# WIFI2UART.net
KiCad netlist of a schematic drawn in Altium Designer
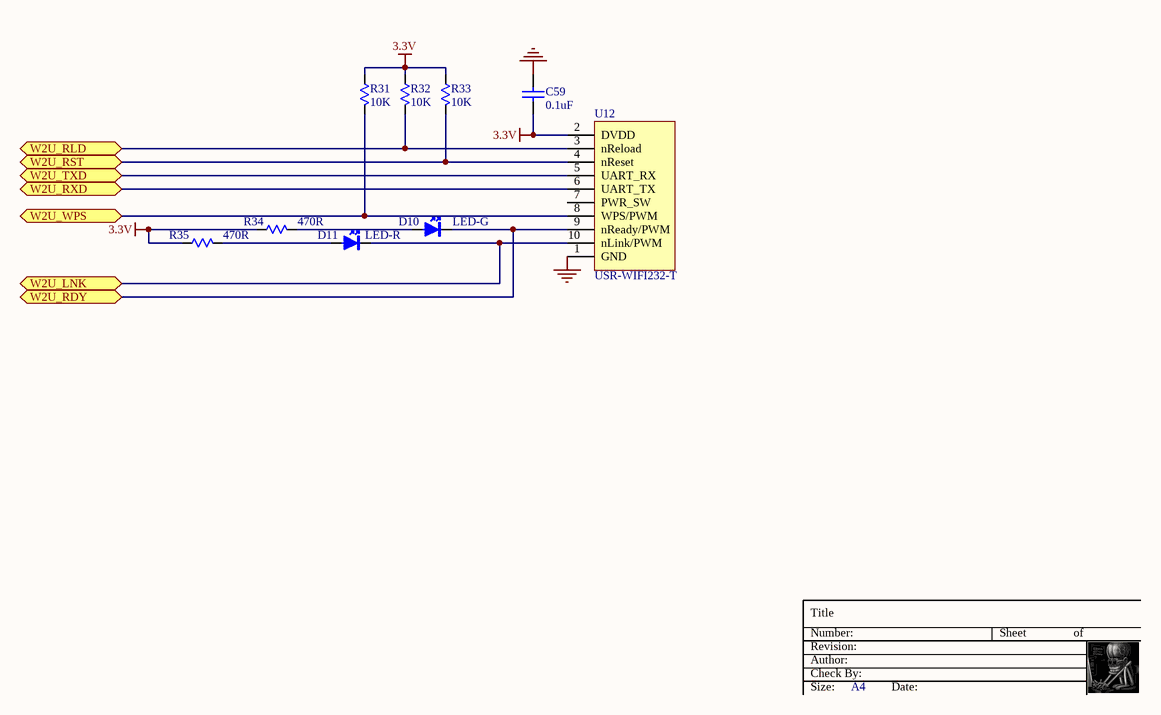
[diagram p0: WIFI2UART.SchDoc]

(export (version "E")
  (design (tool "Eeschema 10.0.6"))
  (components
    (comp (ref "C59")
      (value "0.1uF")
      (footprint "C0603-S")
      (description "Capacitor")
      (libsource (lib "Passive Components Class") (part "CAP"))
    )
    (comp (ref "D10")
      (value "LED-G")
      (footprint "LED0603")
      (description "Light Emitting Diode")
      (libsource (lib "Passive Components Class") (part "LED"))
    )
    (comp (ref "D11")
      (value "LED-R")
      (footprint "LED0603")
      (description "Light Emitting Diode")
      (libsource (lib "Passive Components Class") (part "LED"))
    )
    (comp (ref "R31")
      (value "10K")
      (footprint "R0603-S")
      (description "Resistor")
      (libsource (lib "Passive Components Class") (part "RES"))
    )
    (comp (ref "R32")
      (value "10K")
      (footprint "R0603-S")
      (description "Resistor")
      (libsource (lib "Passive Components Class") (part "RES"))
    )
    (comp (ref "R33")
      (value "10K")
      (footprint "R0603-S")
      (description "Resistor")
      (libsource (lib "Passive Components Class") (part "RES"))
    )
    (comp (ref "R34")
      (value "470R")
      (footprint "R0603-S")
      (description "Resistor")
      (libsource (lib "Passive Components Class") (part "RES"))
    )
    (comp (ref "R35")
      (value "470R")
      (footprint "R0603-S")
      (description "Resistor")
      (libsource (lib "Passive Components Class") (part "RES"))
    )
    (comp (ref "U12")
      (value "USR-WIFI232-T")
      (footprint "USR-WIFI232-T")
      (libsource (lib "RF Class") (part "USR-WIFI232-T"))
    )
  )
  (nets
    (net (code "1") (name "/W2U_LNK") (class "Default")
      (node (ref "D11") (pin "2") (pinfunction "K_2") (pintype "passive"))
      (node (ref "U12") (pin "10") (pinfunction "nLink/PWM_10") (pintype "passive"))
    )
    (net (code "2") (name "/W2U_RDY") (class "Default")
      (node (ref "D10") (pin "2") (pinfunction "K_2") (pintype "passive"))
      (node (ref "U12") (pin "9") (pinfunction "nReady/PWM_9") (pintype "passive"))
    )
    (net (code "3") (name "/W2U_RLD") (class "Default")
      (node (ref "R32") (pin "1") (pinfunction "1_1") (pintype "passive"))
      (node (ref "U12") (pin "3") (pinfunction "nReload_3") (pintype "passive"))
    )
    (net (code "4") (name "/W2U_RST") (class "Default")
      (node (ref "R33") (pin "1") (pinfunction "1_1") (pintype "passive"))
      (node (ref "U12") (pin "4") (pinfunction "nReset_4") (pintype "passive"))
    )
    (net (code "5") (name "/W2U_RXD") (class "Default")
      (node (ref "U12") (pin "6") (pinfunction "UART_TX_6") (pintype "passive"))
    )
    (net (code "6") (name "/W2U_TXD") (class "Default")
      (node (ref "U12") (pin "5") (pinfunction "UART_RX_5") (pintype "passive"))
    )
    (net (code "7") (name "/W2U_WPS") (class "Default")
      (node (ref "R31") (pin "1") (pinfunction "1_1") (pintype "passive"))
      (node (ref "U12") (pin "8") (pinfunction "WPS/PWM_8") (pintype "passive"))
    )
    (net (code "8") (name "3.3V") (class "Default")
      (node (ref "C59") (pin "1") (pinfunction "1_1") (pintype "passive"))
      (node (ref "R31") (pin "2") (pinfunction "2_2") (pintype "passive"))
      (node (ref "R32") (pin "2") (pinfunction "2_2") (pintype "passive"))
      (node (ref "R33") (pin "2") (pinfunction "2_2") (pintype "passive"))
      (node (ref "R34") (pin "2") (pinfunction "2_2") (pintype "passive"))
      (node (ref "R35") (pin "2") (pinfunction "2_2") (pintype "passive"))
      (node (ref "U12") (pin "2") (pinfunction "DVDD_2") (pintype "passive"))
    )
    (net (code "9") (name "GND") (class "Default")
      (node (ref "C59") (pin "2") (pinfunction "2_2") (pintype "passive"))
      (node (ref "U12") (pin "1") (pinfunction "GND_1") (pintype "passive"))
    )
    (net (code "10") (name "Net-(D10-A)") (class "Default")
      (node (ref "D10") (pin "1") (pinfunction "A_1") (pintype "passive"))
      (node (ref "R34") (pin "1") (pinfunction "1_1") (pintype "passive"))
    )
    (net (code "11") (name "Net-(D11-A)") (class "Default")
      (node (ref "D11") (pin "1") (pinfunction "A_1") (pintype "passive"))
      (node (ref "R35") (pin "1") (pinfunction "1_1") (pintype "passive"))
    )
    (net (code "12") (name "unconnected-(U12-PWR_SW-Pad7)") (class "Default")
      (node (ref "U12") (pin "7") (pinfunction "PWR_SW_7") (pintype "passive"))
    )
  )
)
